# main.net
KiCad netlist of a schematic drawn in EAGLE
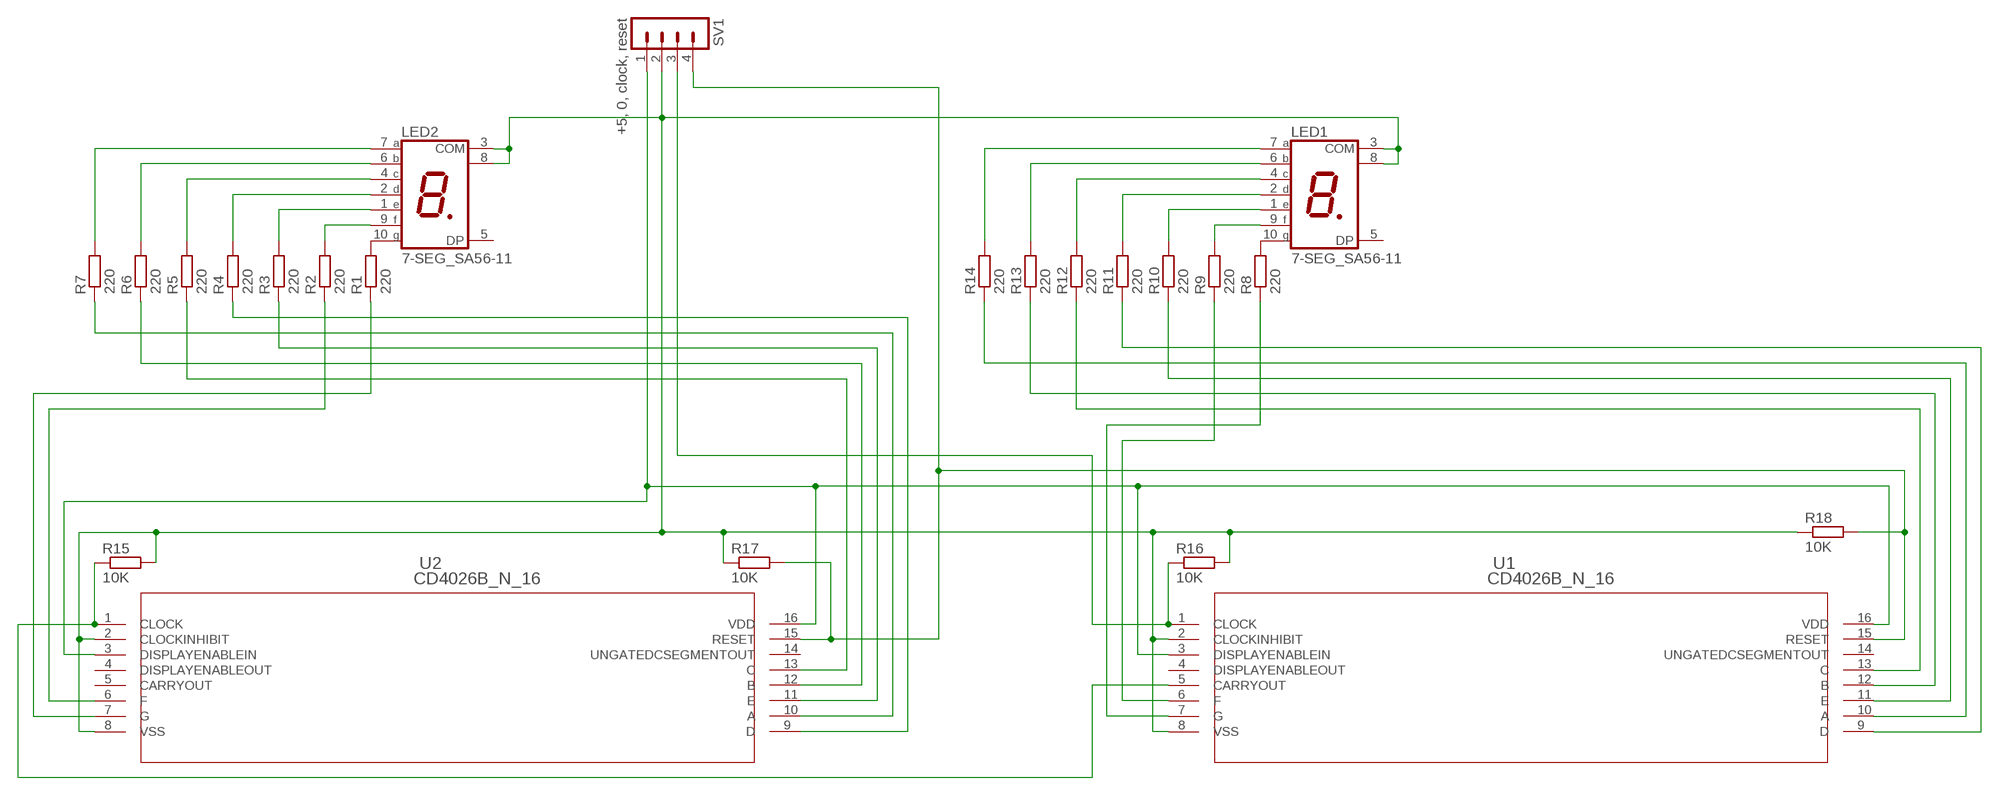
[diagram p0: schematic, sheet 1]

(export (version "E")
  (design (tool "Eeschema 10.0.6"))
  (components
    (comp (ref "LED1")
      (value "7-SEG_SA56-11")
      (footprint "eagle-import:SA56-11")
      (libsource (lib "eagle-import") (part "7-SEG_SA56-11"))
    )
    (comp (ref "LED2")
      (value "7-SEG_SA56-11")
      (footprint "eagle-import:SA56-11")
      (libsource (lib "eagle-import") (part "7-SEG_SA56-11"))
    )
    (comp (ref "R1")
      (value "220")
      (footprint "eagle-import:R0805")
      (libsource (lib "eagle-import") (part "R-EU_R0805"))
    )
    (comp (ref "R2")
      (value "220")
      (footprint "eagle-import:R0805")
      (libsource (lib "eagle-import") (part "R-EU_R0805"))
    )
    (comp (ref "R3")
      (value "220")
      (footprint "eagle-import:R0805")
      (libsource (lib "eagle-import") (part "R-EU_R0805"))
    )
    (comp (ref "R4")
      (value "220")
      (footprint "eagle-import:R0805")
      (libsource (lib "eagle-import") (part "R-EU_R0805"))
    )
    (comp (ref "R5")
      (value "220")
      (footprint "eagle-import:R0805")
      (libsource (lib "eagle-import") (part "R-EU_R0805"))
    )
    (comp (ref "R6")
      (value "220")
      (footprint "eagle-import:R0805")
      (libsource (lib "eagle-import") (part "R-EU_R0805"))
    )
    (comp (ref "R7")
      (value "220")
      (footprint "eagle-import:R0805")
      (libsource (lib "eagle-import") (part "R-EU_R0805"))
    )
    (comp (ref "R8")
      (value "220")
      (footprint "eagle-import:R0805")
      (libsource (lib "eagle-import") (part "R-EU_R0805"))
    )
    (comp (ref "R9")
      (value "220")
      (footprint "eagle-import:R0805")
      (libsource (lib "eagle-import") (part "R-EU_R0805"))
    )
    (comp (ref "R10")
      (value "220")
      (footprint "eagle-import:R0805")
      (libsource (lib "eagle-import") (part "R-EU_R0805"))
    )
    (comp (ref "R11")
      (value "220")
      (footprint "eagle-import:R0805")
      (libsource (lib "eagle-import") (part "R-EU_R0805"))
    )
    (comp (ref "R12")
      (value "220")
      (footprint "eagle-import:R0805")
      (libsource (lib "eagle-import") (part "R-EU_R0805"))
    )
    (comp (ref "R13")
      (value "220")
      (footprint "eagle-import:R0805")
      (libsource (lib "eagle-import") (part "R-EU_R0805"))
    )
    (comp (ref "R14")
      (value "220")
      (footprint "eagle-import:R0805")
      (libsource (lib "eagle-import") (part "R-EU_R0805"))
    )
    (comp (ref "R15")
      (value "10K")
      (footprint "eagle-import:R0805")
      (libsource (lib "eagle-import") (part "R-EU_R0805"))
    )
    (comp (ref "R16")
      (value "10K")
      (footprint "eagle-import:R0805")
      (libsource (lib "eagle-import") (part "R-EU_R0805"))
    )
    (comp (ref "R17")
      (value "10K")
      (footprint "eagle-import:R0805")
      (libsource (lib "eagle-import") (part "R-EU_R0805"))
    )
    (comp (ref "R18")
      (value "10K")
      (footprint "eagle-import:R0805")
      (libsource (lib "eagle-import") (part "R-EU_R0805"))
    )
    (comp (ref "SV1")
      (value "+5, 0, clock, reset")
      (footprint "eagle-import:MA04-1")
      (libsource (lib "eagle-import") (part "MA04-1"))
    )
    (comp (ref "U1")
      (value "CD4026B_N_16")
      (footprint "eagle-import:N16")
      (fields
        (field (name "GENERIC_PART_NUMBER") "CD4026B")
        (field (name "MANUFACTURER") "Texas Instruments")
      )
      (libsource (lib "eagle-import") (part "CD4026B_N_16"))
    )
    (comp (ref "U2")
      (value "CD4026B_N_16")
      (footprint "eagle-import:N16")
      (fields
        (field (name "GENERIC_PART_NUMBER") "CD4026B")
        (field (name "MANUFACTURER") "Texas Instruments")
      )
      (libsource (lib "eagle-import") (part "CD4026B_N_16"))
    )
  )
  (nets
    (net (code "1") (name "Net-(LED1-A)") (class "Default")
      (node (ref "LED1") (pin "7") (pinfunction "A_7") (pintype "passive"))
      (node (ref "R14") (pin "2") (pinfunction "2_2") (pintype "passive"))
    )
    (net (code "2") (name "Net-(LED1-B)") (class "Default")
      (node (ref "LED1") (pin "6") (pinfunction "B_6") (pintype "passive"))
      (node (ref "R13") (pin "2") (pinfunction "2_2") (pintype "passive"))
    )
    (net (code "3") (name "Net-(LED1-C)") (class "Default")
      (node (ref "LED1") (pin "4") (pinfunction "C_4") (pintype "passive"))
      (node (ref "R12") (pin "2") (pinfunction "2_2") (pintype "passive"))
    )
    (net (code "4") (name "Net-(LED1-D)") (class "Default")
      (node (ref "LED1") (pin "2") (pinfunction "D_2") (pintype "passive"))
      (node (ref "R11") (pin "2") (pinfunction "2_2") (pintype "passive"))
    )
    (net (code "5") (name "Net-(LED1-E)") (class "Default")
      (node (ref "LED1") (pin "1") (pinfunction "E_1") (pintype "passive"))
      (node (ref "R10") (pin "2") (pinfunction "2_2") (pintype "passive"))
    )
    (net (code "6") (name "Net-(LED1-F)") (class "Default")
      (node (ref "LED1") (pin "9") (pinfunction "F_9") (pintype "passive"))
      (node (ref "R9") (pin "2") (pinfunction "2_2") (pintype "passive"))
    )
    (net (code "7") (name "Net-(LED1-G)") (class "Default")
      (node (ref "LED1") (pin "10") (pinfunction "G_10") (pintype "passive"))
      (node (ref "R8") (pin "2") (pinfunction "2_2") (pintype "passive"))
    )
    (net (code "8") (name "Net-(LED2-A)") (class "Default")
      (node (ref "LED2") (pin "7") (pinfunction "A_7") (pintype "passive"))
      (node (ref "R7") (pin "2") (pinfunction "2_2") (pintype "passive"))
    )
    (net (code "9") (name "Net-(LED2-B)") (class "Default")
      (node (ref "LED2") (pin "6") (pinfunction "B_6") (pintype "passive"))
      (node (ref "R6") (pin "2") (pinfunction "2_2") (pintype "passive"))
    )
    (net (code "10") (name "Net-(LED2-C)") (class "Default")
      (node (ref "LED2") (pin "4") (pinfunction "C_4") (pintype "passive"))
      (node (ref "R5") (pin "2") (pinfunction "2_2") (pintype "passive"))
    )
    (net (code "11") (name "Net-(LED2-D)") (class "Default")
      (node (ref "LED2") (pin "2") (pinfunction "D_2") (pintype "passive"))
      (node (ref "R4") (pin "2") (pinfunction "2_2") (pintype "passive"))
    )
    (net (code "12") (name "Net-(LED2-E)") (class "Default")
      (node (ref "LED2") (pin "1") (pinfunction "E_1") (pintype "passive"))
      (node (ref "R3") (pin "2") (pinfunction "2_2") (pintype "passive"))
    )
    (net (code "13") (name "Net-(LED2-F)") (class "Default")
      (node (ref "LED2") (pin "9") (pinfunction "F_9") (pintype "passive"))
      (node (ref "R2") (pin "2") (pinfunction "2_2") (pintype "passive"))
    )
    (net (code "14") (name "Net-(LED2-G)") (class "Default")
      (node (ref "LED2") (pin "10") (pinfunction "G_10") (pintype "passive"))
      (node (ref "R1") (pin "2") (pinfunction "2_2") (pintype "passive"))
    )
    (net (code "15") (name "Net-(U1-A)") (class "Default")
      (node (ref "R14") (pin "1") (pinfunction "1_1") (pintype "passive"))
      (node (ref "U1") (pin "10") (pinfunction "A_10") (pintype "passive"))
    )
    (net (code "16") (name "Net-(U1-B)") (class "Default")
      (node (ref "R13") (pin "1") (pinfunction "1_1") (pintype "passive"))
      (node (ref "U1") (pin "12") (pinfunction "B_12") (pintype "passive"))
    )
    (net (code "17") (name "Net-(U1-C)") (class "Default")
      (node (ref "R12") (pin "1") (pinfunction "1_1") (pintype "passive"))
      (node (ref "U1") (pin "13") (pinfunction "C_13") (pintype "passive"))
    )
    (net (code "18") (name "Net-(U1-CARRYOUT)") (class "Default")
      (node (ref "R15") (pin "1") (pinfunction "1_1") (pintype "passive"))
      (node (ref "U1") (pin "5") (pinfunction "CARRYOUT_5") (pintype "output"))
      (node (ref "U2") (pin "1") (pinfunction "CLOCK_1") (pintype "passive"))
    )
    (net (code "19") (name "Net-(U1-CLOCK)") (class "Default")
      (node (ref "R16") (pin "1") (pinfunction "1_1") (pintype "passive"))
      (node (ref "SV1") (pin "3") (pinfunction "3_3") (pintype "passive"))
      (node (ref "U1") (pin "1") (pinfunction "CLOCK_1") (pintype "passive"))
    )
    (net (code "20") (name "Net-(U1-CLOCKINHIBIT)") (class "Default")
      (node (ref "LED1") (pin "3") (pinfunction "COM_3") (pintype "passive"))
      (node (ref "LED1") (pin "8") (pinfunction "COM_8") (pintype "passive"))
      (node (ref "LED2") (pin "3") (pinfunction "COM_3") (pintype "passive"))
      (node (ref "LED2") (pin "8") (pinfunction "COM_8") (pintype "passive"))
      (node (ref "R15") (pin "2") (pinfunction "2_2") (pintype "passive"))
      (node (ref "R16") (pin "2") (pinfunction "2_2") (pintype "passive"))
      (node (ref "R17") (pin "1") (pinfunction "1_1") (pintype "passive"))
      (node (ref "R18") (pin "1") (pinfunction "1_1") (pintype "passive"))
      (node (ref "SV1") (pin "2") (pinfunction "2_2") (pintype "passive"))
      (node (ref "U1") (pin "2") (pinfunction "CLOCKINHIBIT_2") (pintype "passive"))
      (node (ref "U1") (pin "8") (pinfunction "VSS_8") (pintype "power_in"))
      (node (ref "U2") (pin "2") (pinfunction "CLOCKINHIBIT_2") (pintype "passive"))
      (node (ref "U2") (pin "8") (pinfunction "VSS_8") (pintype "power_in"))
    )
    (net (code "21") (name "Net-(U1-D)") (class "Default")
      (node (ref "R11") (pin "1") (pinfunction "1_1") (pintype "passive"))
      (node (ref "U1") (pin "9") (pinfunction "D_9") (pintype "passive"))
    )
    (net (code "22") (name "Net-(U1-DISPLAYENABLEIN)") (class "Default")
      (node (ref "SV1") (pin "1") (pinfunction "1_1") (pintype "passive"))
      (node (ref "U1") (pin "16") (pinfunction "VDD_16") (pintype "power_in"))
      (node (ref "U1") (pin "3") (pinfunction "DISPLAYENABLEIN_3") (pintype "input"))
      (node (ref "U2") (pin "16") (pinfunction "VDD_16") (pintype "power_in"))
      (node (ref "U2") (pin "3") (pinfunction "DISPLAYENABLEIN_3") (pintype "input"))
    )
    (net (code "23") (name "Net-(U1-E)") (class "Default")
      (node (ref "R10") (pin "1") (pinfunction "1_1") (pintype "passive"))
      (node (ref "U1") (pin "11") (pinfunction "E_11") (pintype "passive"))
    )
    (net (code "24") (name "Net-(U1-F)") (class "Default")
      (node (ref "R9") (pin "1") (pinfunction "1_1") (pintype "passive"))
      (node (ref "U1") (pin "6") (pinfunction "F_6") (pintype "passive"))
    )
    (net (code "25") (name "Net-(U1-G)") (class "Default")
      (node (ref "R8") (pin "1") (pinfunction "1_1") (pintype "passive"))
      (node (ref "U1") (pin "7") (pinfunction "G_7") (pintype "passive"))
    )
    (net (code "26") (name "Net-(U1-RESET)") (class "Default")
      (node (ref "R17") (pin "2") (pinfunction "2_2") (pintype "passive"))
      (node (ref "R18") (pin "2") (pinfunction "2_2") (pintype "passive"))
      (node (ref "SV1") (pin "4") (pinfunction "4_4") (pintype "passive"))
      (node (ref "U1") (pin "15") (pinfunction "RESET_15") (pintype "passive"))
      (node (ref "U2") (pin "15") (pinfunction "RESET_15") (pintype "passive"))
    )
    (net (code "27") (name "Net-(U2-A)") (class "Default")
      (node (ref "R7") (pin "1") (pinfunction "1_1") (pintype "passive"))
      (node (ref "U2") (pin "10") (pinfunction "A_10") (pintype "passive"))
    )
    (net (code "28") (name "Net-(U2-B)") (class "Default")
      (node (ref "R6") (pin "1") (pinfunction "1_1") (pintype "passive"))
      (node (ref "U2") (pin "12") (pinfunction "B_12") (pintype "passive"))
    )
    (net (code "29") (name "Net-(U2-C)") (class "Default")
      (node (ref "R5") (pin "1") (pinfunction "1_1") (pintype "passive"))
      (node (ref "U2") (pin "13") (pinfunction "C_13") (pintype "passive"))
    )
    (net (code "30") (name "Net-(U2-D)") (class "Default")
      (node (ref "R4") (pin "1") (pinfunction "1_1") (pintype "passive"))
      (node (ref "U2") (pin "9") (pinfunction "D_9") (pintype "passive"))
    )
    (net (code "31") (name "Net-(U2-E)") (class "Default")
      (node (ref "R3") (pin "1") (pinfunction "1_1") (pintype "passive"))
      (node (ref "U2") (pin "11") (pinfunction "E_11") (pintype "passive"))
    )
    (net (code "32") (name "Net-(U2-F)") (class "Default")
      (node (ref "R2") (pin "1") (pinfunction "1_1") (pintype "passive"))
      (node (ref "U2") (pin "6") (pinfunction "F_6") (pintype "passive"))
    )
    (net (code "33") (name "Net-(U2-G)") (class "Default")
      (node (ref "R1") (pin "1") (pinfunction "1_1") (pintype "passive"))
      (node (ref "U2") (pin "7") (pinfunction "G_7") (pintype "passive"))
    )
    (net (code "34") (name "unconnected-(LED1-DP-Pad5)") (class "Default")
      (node (ref "LED1") (pin "5") (pinfunction "DP_5") (pintype "passive"))
    )
    (net (code "35") (name "unconnected-(LED2-DP-Pad5)") (class "Default")
      (node (ref "LED2") (pin "5") (pinfunction "DP_5") (pintype "passive"))
    )
    (net (code "36") (name "unconnected-(U1-DISPLAYENABLEOUT-Pad4)") (class "Default")
      (node (ref "U1") (pin "4") (pinfunction "DISPLAYENABLEOUT_4") (pintype "output"))
    )
    (net (code "37") (name "unconnected-(U1-UNGATEDCSEGMENTOUT-Pad14)") (class "Default")
      (node (ref "U1") (pin "14") (pinfunction "UNGATEDCSEGMENTOUT_14") (pintype "output"))
    )
    (net (code "38") (name "unconnected-(U2-CARRYOUT-Pad5)") (class "Default")
      (node (ref "U2") (pin "5") (pinfunction "CARRYOUT_5") (pintype "output"))
    )
    (net (code "39") (name "unconnected-(U2-DISPLAYENABLEOUT-Pad4)") (class "Default")
      (node (ref "U2") (pin "4") (pinfunction "DISPLAYENABLEOUT_4") (pintype "output"))
    )
    (net (code "40") (name "unconnected-(U2-UNGATEDCSEGMENTOUT-Pad14)") (class "Default")
      (node (ref "U2") (pin "14") (pinfunction "UNGATEDCSEGMENTOUT_14") (pintype "output"))
    )
  )
)
